# mux.net
KiCad netlist of a schematic drawn in EAGLE
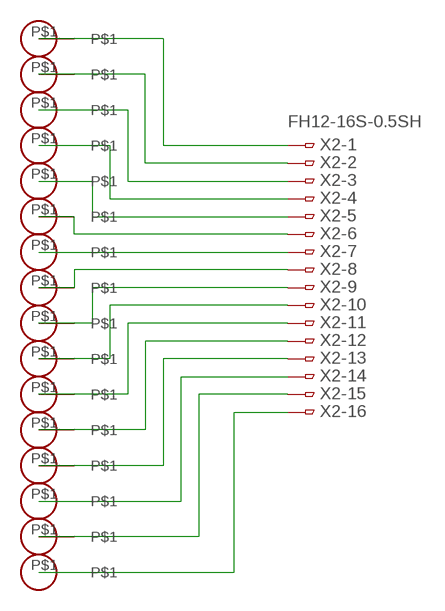
[diagram p0: schematic, sheet 1]

(export (version "E")
  (design (tool "Eeschema 10.0.6"))
  (components
    (comp (ref "U$1")
      (value "PADPAD")
      (footprint "eagle-import:PAD")
      (libsource (lib "eagle-import") (part "PADPAD"))
    )
    (comp (ref "U$2")
      (value "PADPAD")
      (footprint "eagle-import:PAD")
      (libsource (lib "eagle-import") (part "PADPAD"))
    )
    (comp (ref "U$3")
      (value "PADPAD")
      (footprint "eagle-import:PAD")
      (libsource (lib "eagle-import") (part "PADPAD"))
    )
    (comp (ref "U$4")
      (value "PADPAD")
      (footprint "eagle-import:PAD")
      (libsource (lib "eagle-import") (part "PADPAD"))
    )
    (comp (ref "U$5")
      (value "PADPAD")
      (footprint "eagle-import:PAD")
      (libsource (lib "eagle-import") (part "PADPAD"))
    )
    (comp (ref "U$6")
      (value "PADPAD")
      (footprint "eagle-import:PAD")
      (libsource (lib "eagle-import") (part "PADPAD"))
    )
    (comp (ref "U$7")
      (value "PADPAD")
      (footprint "eagle-import:PAD")
      (libsource (lib "eagle-import") (part "PADPAD"))
    )
    (comp (ref "U$8")
      (value "PADPAD")
      (footprint "eagle-import:PAD")
      (libsource (lib "eagle-import") (part "PADPAD"))
    )
    (comp (ref "U$9")
      (value "PADPAD")
      (footprint "eagle-import:PAD")
      (libsource (lib "eagle-import") (part "PADPAD"))
    )
    (comp (ref "U$10")
      (value "PADPAD")
      (footprint "eagle-import:PAD")
      (libsource (lib "eagle-import") (part "PADPAD"))
    )
    (comp (ref "U$11")
      (value "PADPAD")
      (footprint "eagle-import:PAD")
      (libsource (lib "eagle-import") (part "PADPAD"))
    )
    (comp (ref "U$12")
      (value "PADPAD")
      (footprint "eagle-import:PAD")
      (libsource (lib "eagle-import") (part "PADPAD"))
    )
    (comp (ref "U$13")
      (value "PADPAD")
      (footprint "eagle-import:PAD")
      (libsource (lib "eagle-import") (part "PADPAD"))
    )
    (comp (ref "U$14")
      (value "PADPAD")
      (footprint "eagle-import:PAD")
      (libsource (lib "eagle-import") (part "PADPAD"))
    )
    (comp (ref "U$15")
      (value "PADPAD")
      (footprint "eagle-import:PAD")
      (libsource (lib "eagle-import") (part "PADPAD"))
    )
    (comp (ref "U$16")
      (value "PADPAD")
      (footprint "eagle-import:PAD")
      (libsource (lib "eagle-import") (part "PADPAD"))
    )
    (comp (ref "X2")
      (value "FH12-16S-0.5SH")
      (footprint "eagle-import:FH12-16S-0.5SH")
      (fields (field (name "MPN") "FH12-16S-0.5SH(55)"))
      (libsource (lib "eagle-import") (part "FH12-16S-0.5SH"))
    )
  )
  (nets
    (net (code "1") (name "Net-(U$1-PadP$1)") (class "Default")
      (node (ref "U$1") (pin "P$1") (pinfunction "P$1_P$1") (pintype "bidirectional"))
      (node (ref "X2") (pin "1") (pinfunction "1_1") (pintype "passive"))
    )
    (net (code "2") (name "Net-(X2B-1)") (class "Default")
      (node (ref "U$10") (pin "P$1") (pinfunction "P$1_P$1") (pintype "bidirectional"))
      (node (ref "X2") (pin "10") (pinfunction "1_10") (pintype "passive"))
    )
    (net (code "3") (name "Net-(X2C-1)") (class "Default")
      (node (ref "U$11") (pin "P$1") (pinfunction "P$1_P$1") (pintype "bidirectional"))
      (node (ref "X2") (pin "11") (pinfunction "1_11") (pintype "passive"))
    )
    (net (code "4") (name "Net-(X2D-1)") (class "Default")
      (node (ref "U$12") (pin "P$1") (pinfunction "P$1_P$1") (pintype "bidirectional"))
      (node (ref "X2") (pin "12") (pinfunction "1_12") (pintype "passive"))
    )
    (net (code "5") (name "Net-(X2E-1)") (class "Default")
      (node (ref "U$13") (pin "P$1") (pinfunction "P$1_P$1") (pintype "bidirectional"))
      (node (ref "X2") (pin "13") (pinfunction "1_13") (pintype "passive"))
    )
    (net (code "6") (name "Net-(X2F-1)") (class "Default")
      (node (ref "U$14") (pin "P$1") (pinfunction "P$1_P$1") (pintype "bidirectional"))
      (node (ref "X2") (pin "14") (pinfunction "1_14") (pintype "passive"))
    )
    (net (code "7") (name "Net-(X2G-1)") (class "Default")
      (node (ref "U$15") (pin "P$1") (pinfunction "P$1_P$1") (pintype "bidirectional"))
      (node (ref "X2") (pin "15") (pinfunction "1_15") (pintype "passive"))
    )
    (net (code "8") (name "Net-(X2H-1)") (class "Default")
      (node (ref "U$16") (pin "P$1") (pinfunction "P$1_P$1") (pintype "bidirectional"))
      (node (ref "X2") (pin "16") (pinfunction "1_16") (pintype "passive"))
    )
    (net (code "9") (name "Net-(X2I-1)") (class "Default")
      (node (ref "U$2") (pin "P$1") (pinfunction "P$1_P$1") (pintype "bidirectional"))
      (node (ref "X2") (pin "2") (pinfunction "1_2") (pintype "passive"))
    )
    (net (code "10") (name "Net-(X2J-1)") (class "Default")
      (node (ref "U$3") (pin "P$1") (pinfunction "P$1_P$1") (pintype "bidirectional"))
      (node (ref "X2") (pin "3") (pinfunction "1_3") (pintype "passive"))
    )
    (net (code "11") (name "Net-(X2K-1)") (class "Default")
      (node (ref "U$4") (pin "P$1") (pinfunction "P$1_P$1") (pintype "bidirectional"))
      (node (ref "X2") (pin "4") (pinfunction "1_4") (pintype "passive"))
    )
    (net (code "12") (name "Net-(X2L-1)") (class "Default")
      (node (ref "U$5") (pin "P$1") (pinfunction "P$1_P$1") (pintype "bidirectional"))
      (node (ref "X2") (pin "5") (pinfunction "1_5") (pintype "passive"))
    )
    (net (code "13") (name "Net-(X2M-1)") (class "Default")
      (node (ref "U$6") (pin "P$1") (pinfunction "P$1_P$1") (pintype "bidirectional"))
      (node (ref "X2") (pin "6") (pinfunction "1_6") (pintype "passive"))
    )
    (net (code "14") (name "Net-(X2N-1)") (class "Default")
      (node (ref "U$7") (pin "P$1") (pinfunction "P$1_P$1") (pintype "bidirectional"))
      (node (ref "X2") (pin "7") (pinfunction "1_7") (pintype "passive"))
    )
    (net (code "15") (name "Net-(X2O-1)") (class "Default")
      (node (ref "U$8") (pin "P$1") (pinfunction "P$1_P$1") (pintype "bidirectional"))
      (node (ref "X2") (pin "8") (pinfunction "1_8") (pintype "passive"))
    )
    (net (code "16") (name "Net-(X2P-1)") (class "Default")
      (node (ref "U$9") (pin "P$1") (pinfunction "P$1_P$1") (pintype "bidirectional"))
      (node (ref "X2") (pin "9") (pinfunction "1_9") (pintype "passive"))
    )
  )
)
